# Mono_i2c_v2_TEMP.net
KiCad netlist of a schematic drawn in EAGLE
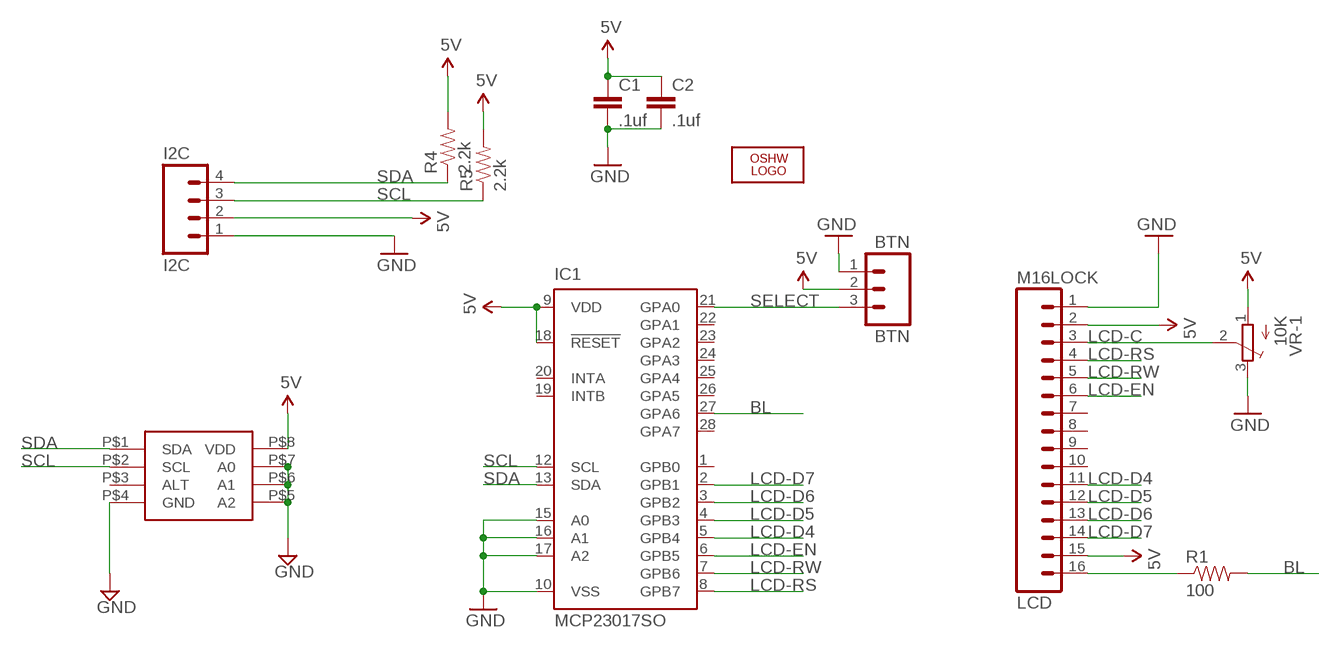
[diagram p0: schematic, sheet 1]

(export (version "E")
  (design (tool "Eeschema 10.0.6"))
  (components
    (comp (ref "BTN")
      (value "BTN")
      (footprint "eagle-import:1X03_LOCK")
      (libsource (lib "eagle-import") (part "M03LOCK"))
    )
    (comp (ref "C1")
      (value ".1uf")
      (footprint "eagle-import:0805")
      (libsource (lib "eagle-import") (part "CAP0805"))
    )
    (comp (ref "C2")
      (value ".1uf")
      (footprint "eagle-import:0805")
      (libsource (lib "eagle-import") (part "CAP0805"))
    )
    (comp (ref "I2C")
      (value "I2C")
      (footprint "eagle-import:1X04_LOCK")
      (libsource (lib "eagle-import") (part "M04LOCK"))
    )
    (comp (ref "IC1")
      (value "MCP23017SO")
      (footprint "eagle-import:SO28W")
      (libsource (lib "eagle-import") (part "MCP23017SO"))
    )
    (comp (ref "IC2")
      (value "MCP9808")
      (footprint "eagle-import:MSOP8")
      (libsource (lib "eagle-import") (part "MCP9808"))
    )
    (comp (ref "LCD")
      (value "M16LOCK")
      (footprint "eagle-import:1X16_LOCK")
      (libsource (lib "eagle-import") (part "M16LOCK"))
    )
    (comp (ref "LOGO2")
      (value "OSHW_LOGO_10MILX0350-NT")
      (footprint "eagle-import:OSHW_10X350_NOTEXT")
      (libsource (lib "eagle-import") (part "OSHW_LOGO_10MILX0350-NT"))
    )
    (comp (ref "R1")
      (value "100")
      (footprint "eagle-import:0805")
      (libsource (lib "eagle-import") (part "RESISTOR0805-RES"))
    )
    (comp (ref "R4")
      (value "2.2k")
      (footprint "eagle-import:0805")
      (libsource (lib "eagle-import") (part "RESISTOR0805-RES"))
    )
    (comp (ref "R5")
      (value "2.2k")
      (footprint "eagle-import:0805")
      (libsource (lib "eagle-import") (part "RESISTOR0805-RES"))
    )
    (comp (ref "VR-1")
      (value "10K")
      (footprint "eagle-import:TC33X")
      (libsource (lib "eagle-import") (part "TRIMPOTTC33X"))
    )
  )
  (nets
    (net (code "1") (name "/BL") (class "Default")
      (node (ref "IC1") (pin "27") (pinfunction "GPA6_27") (pintype "bidirectional"))
      (node (ref "R1") (pin "2") (pinfunction "2_2") (pintype "passive"))
    )
    (net (code "2") (name "/LCD-C") (class "Default")
      (node (ref "LCD") (pin "3") (pinfunction "3_3") (pintype "passive"))
      (node (ref "VR-1") (pin "2") (pinfunction "S_2") (pintype "passive"))
    )
    (net (code "3") (name "/LCD-D4") (class "Default")
      (node (ref "IC1") (pin "5") (pinfunction "GPB4_5") (pintype "bidirectional"))
      (node (ref "LCD") (pin "11") (pinfunction "11_11") (pintype "passive"))
    )
    (net (code "4") (name "/LCD-D5") (class "Default")
      (node (ref "IC1") (pin "4") (pinfunction "GPB3_4") (pintype "bidirectional"))
      (node (ref "LCD") (pin "12") (pinfunction "12_12") (pintype "passive"))
    )
    (net (code "5") (name "/LCD-D6") (class "Default")
      (node (ref "IC1") (pin "3") (pinfunction "GPB2_3") (pintype "bidirectional"))
      (node (ref "LCD") (pin "13") (pinfunction "13_13") (pintype "passive"))
    )
    (net (code "6") (name "/LCD-D7") (class "Default")
      (node (ref "IC1") (pin "2") (pinfunction "GPB1_2") (pintype "bidirectional"))
      (node (ref "LCD") (pin "14") (pinfunction "14_14") (pintype "passive"))
    )
    (net (code "7") (name "/LCD-EN") (class "Default")
      (node (ref "IC1") (pin "6") (pinfunction "GPB5_6") (pintype "bidirectional"))
      (node (ref "LCD") (pin "6") (pinfunction "6_6") (pintype "passive"))
    )
    (net (code "8") (name "/LCD-RS") (class "Default")
      (node (ref "IC1") (pin "8") (pinfunction "GPB7_8") (pintype "bidirectional"))
      (node (ref "LCD") (pin "4") (pinfunction "4_4") (pintype "passive"))
    )
    (net (code "9") (name "/LCD-RW") (class "Default")
      (node (ref "IC1") (pin "7") (pinfunction "GPB6_7") (pintype "bidirectional"))
      (node (ref "LCD") (pin "5") (pinfunction "5_5") (pintype "passive"))
    )
    (net (code "10") (name "/SCL") (class "Default")
      (node (ref "I2C") (pin "3") (pinfunction "3_3") (pintype "passive"))
      (node (ref "IC1") (pin "12") (pinfunction "SCL_12") (pintype "input"))
      (node (ref "IC2") (pin "P$2") (pinfunction "SCL_P$2") (pintype "bidirectional"))
      (node (ref "R5") (pin "1") (pinfunction "1_1") (pintype "passive"))
    )
    (net (code "11") (name "/SDA") (class "Default")
      (node (ref "I2C") (pin "4") (pinfunction "4_4") (pintype "passive"))
      (node (ref "IC1") (pin "13") (pinfunction "SDA_13") (pintype "bidirectional"))
      (node (ref "IC2") (pin "P$1") (pinfunction "SDA_P$1") (pintype "bidirectional"))
      (node (ref "R4") (pin "1") (pinfunction "1_1") (pintype "passive"))
    )
    (net (code "12") (name "/SELECT") (class "Default")
      (node (ref "BTN") (pin "3") (pinfunction "3_3") (pintype "passive"))
      (node (ref "IC1") (pin "21") (pinfunction "GPA0_21") (pintype "bidirectional"))
    )
    (net (code "13") (name "5V") (class "Default")
      (node (ref "BTN") (pin "2") (pinfunction "2_2") (pintype "passive"))
      (node (ref "C1") (pin "1") (pinfunction "1_1") (pintype "passive"))
      (node (ref "C2") (pin "1") (pinfunction "1_1") (pintype "passive"))
      (node (ref "I2C") (pin "2") (pinfunction "2_2") (pintype "passive"))
      (node (ref "IC1") (pin "18") (pinfunction "~{RESET}_18") (pintype "input"))
      (node (ref "IC1") (pin "9") (pinfunction "VDD_9") (pintype "power_in"))
      (node (ref "IC2") (pin "P$8") (pinfunction "VDD_P$8") (pintype "bidirectional"))
      (node (ref "LCD") (pin "15") (pinfunction "15_15") (pintype "passive"))
      (node (ref "LCD") (pin "2") (pinfunction "2_2") (pintype "passive"))
      (node (ref "R4") (pin "2") (pinfunction "2_2") (pintype "passive"))
      (node (ref "R5") (pin "2") (pinfunction "2_2") (pintype "passive"))
      (node (ref "VR-1") (pin "1") (pinfunction "A_1") (pintype "passive"))
    )
    (net (code "14") (name "GND") (class "Default")
      (node (ref "BTN") (pin "1") (pinfunction "1_1") (pintype "passive"))
      (node (ref "C1") (pin "2") (pinfunction "2_2") (pintype "passive"))
      (node (ref "C2") (pin "2") (pinfunction "2_2") (pintype "passive"))
      (node (ref "I2C") (pin "1") (pinfunction "1_1") (pintype "passive"))
      (node (ref "IC1") (pin "10") (pinfunction "VSS_10") (pintype "power_in"))
      (node (ref "IC1") (pin "15") (pinfunction "A0_15") (pintype "input"))
      (node (ref "IC1") (pin "16") (pinfunction "A1_16") (pintype "input"))
      (node (ref "IC1") (pin "17") (pinfunction "A2_17") (pintype "input"))
      (node (ref "IC2") (pin "P$4") (pinfunction "GND_P$4") (pintype "bidirectional"))
      (node (ref "IC2") (pin "P$5") (pinfunction "A2_P$5") (pintype "bidirectional"))
      (node (ref "IC2") (pin "P$6") (pinfunction "A1_P$6") (pintype "bidirectional"))
      (node (ref "IC2") (pin "P$7") (pinfunction "A0_P$7") (pintype "bidirectional"))
      (node (ref "LCD") (pin "1") (pinfunction "1_1") (pintype "passive"))
      (node (ref "VR-1") (pin "3") (pinfunction "E_3") (pintype "passive"))
    )
    (net (code "15") (name "Net-(LCD-Pad16)") (class "Default")
      (node (ref "LCD") (pin "16") (pinfunction "16_16") (pintype "passive"))
      (node (ref "R1") (pin "1") (pinfunction "1_1") (pintype "passive"))
    )
    (net (code "16") (name "unconnected-(IC1-GPA1-Pad22)") (class "Default")
      (node (ref "IC1") (pin "22") (pinfunction "GPA1_22") (pintype "bidirectional"))
    )
    (net (code "17") (name "unconnected-(IC1-GPA2-Pad23)") (class "Default")
      (node (ref "IC1") (pin "23") (pinfunction "GPA2_23") (pintype "bidirectional"))
    )
    (net (code "18") (name "unconnected-(IC1-GPA3-Pad24)") (class "Default")
      (node (ref "IC1") (pin "24") (pinfunction "GPA3_24") (pintype "bidirectional"))
    )
    (net (code "19") (name "unconnected-(IC1-GPA4-Pad25)") (class "Default")
      (node (ref "IC1") (pin "25") (pinfunction "GPA4_25") (pintype "bidirectional"))
    )
    (net (code "20") (name "unconnected-(IC1-GPA5-Pad26)") (class "Default")
      (node (ref "IC1") (pin "26") (pinfunction "GPA5_26") (pintype "bidirectional"))
    )
    (net (code "21") (name "unconnected-(IC1-GPA7-Pad28)") (class "Default")
      (node (ref "IC1") (pin "28") (pinfunction "GPA7_28") (pintype "bidirectional"))
    )
    (net (code "22") (name "unconnected-(IC1-GPB0-Pad1)") (class "Default")
      (node (ref "IC1") (pin "1") (pinfunction "GPB0_1") (pintype "bidirectional"))
    )
    (net (code "23") (name "unconnected-(IC1-INTA-Pad20)") (class "Default")
      (node (ref "IC1") (pin "20") (pinfunction "INTA_20") (pintype "output"))
    )
    (net (code "24") (name "unconnected-(IC1-INTB-Pad19)") (class "Default")
      (node (ref "IC1") (pin "19") (pinfunction "INTB_19") (pintype "output"))
    )
    (net (code "25") (name "unconnected-(IC2-ALT-PadP$3)") (class "Default")
      (node (ref "IC2") (pin "P$3") (pinfunction "ALT_P$3") (pintype "bidirectional"))
    )
    (net (code "26") (name "unconnected-(LCD-Pad7)") (class "Default")
      (node (ref "LCD") (pin "7") (pinfunction "7_7") (pintype "passive"))
    )
    (net (code "27") (name "unconnected-(LCD-Pad8)") (class "Default")
      (node (ref "LCD") (pin "8") (pinfunction "8_8") (pintype "passive"))
    )
    (net (code "28") (name "unconnected-(LCD-Pad9)") (class "Default")
      (node (ref "LCD") (pin "9") (pinfunction "9_9") (pintype "passive"))
    )
    (net (code "29") (name "unconnected-(LCD-Pad10)") (class "Default")
      (node (ref "LCD") (pin "10") (pinfunction "10_10") (pintype "passive"))
    )
  )
)
